# Drive.net
KiCad netlist of a schematic drawn in Altium Designer
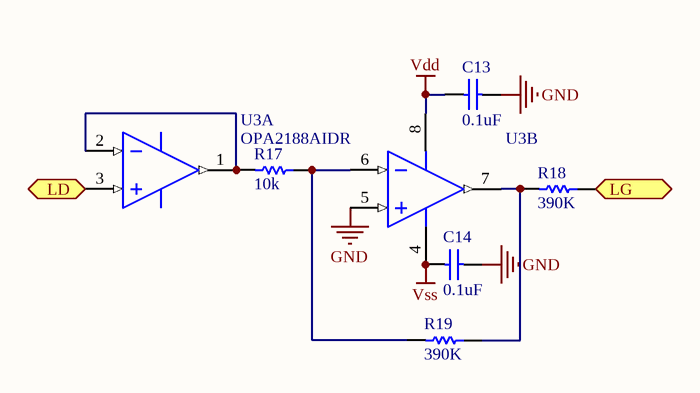
[diagram p0: Drive.SchDoc]

(export (version "E")
  (design (tool "Eeschema 10.0.6"))
  (components
    (comp (ref "C13")
      (value "0.1uF")
      (footprint "C0805")
      (description "Capacitor")
      (fields (field (name "Comment") "Cap") (field (name "PUBLISHER") "Altium Limited"))
      (libsource (lib "Miscellaneous Devices") (part "Cap"))
    )
    (comp (ref "C14")
      (value "0.1uF")
      (footprint "C0805")
      (description "Capacitor")
      (fields (field (name "Comment") "Cap") (field (name "PUBLISHER") "Altium Limited"))
      (libsource (lib "Miscellaneous Devices") (part "Cap"))
    )
    (comp (ref "R17")
      (value "10k")
      (footprint "C1206")
      (description "Resistor")
      (fields (field (name "Comment") "Res1") (field (name "PUBLISHER") "Altium Limited"))
      (libsource (lib "Miscellaneous Devices") (part "Res1"))
    )
    (comp (ref "R18")
      (value "390K")
      (footprint "C1206")
      (description "Resistor")
      (fields (field (name "Comment") "Res1") (field (name "PUBLISHER") "Altium Limited"))
      (libsource (lib "Miscellaneous Devices") (part "Res1"))
    )
    (comp (ref "R19")
      (value "390K")
      (footprint "C1206")
      (description "Resistor")
      (fields (field (name "Comment") "Res1") (field (name "PUBLISHER") "Altium Limited"))
      (libsource (lib "Miscellaneous Devices") (part "Res1"))
    )
    (comp (ref "U3")
      (value "OPA2188AIDR")
      (footprint "TI-D8_N")
      (fields (field (name "MANUFACTURER") "Texas Instruments"))
      (libsource (lib "TI Amplifiers and Linear Operational Amplifier Precision Amplifier Part One") (part "OPA2188AIDR"))
    )
  )
  (nets
    (net (code "1") (name "/LD") (class "Default")
      (node (ref "U3") (pin "3") (pinfunction "IN_A+_3") (pintype "input"))
    )
    (net (code "2") (name "/LG") (class "Default")
      (node (ref "R18") (pin "1") (pinfunction "1_1") (pintype "passive"))
    )
    (net (code "3") (name "GND") (class "Default")
      (node (ref "C13") (pin "1") (pinfunction "1_1") (pintype "passive"))
      (node (ref "C14") (pin "1") (pinfunction "1_1") (pintype "passive"))
      (node (ref "U3") (pin "5") (pinfunction "IN_B+_5") (pintype "input"))
    )
    (net (code "4") (name "Net-(U3A-IN_A-)") (class "Default")
      (node (ref "R17") (pin "2") (pinfunction "2_2") (pintype "passive"))
      (node (ref "U3") (pin "1") (pinfunction "OUT_A_1") (pintype "output"))
      (node (ref "U3") (pin "2") (pinfunction "IN_A-_2") (pintype "input"))
    )
    (net (code "5") (name "Net-(U3B-IN_B-)") (class "Default")
      (node (ref "R17") (pin "1") (pinfunction "1_1") (pintype "passive"))
      (node (ref "R19") (pin "2") (pinfunction "2_2") (pintype "passive"))
      (node (ref "U3") (pin "6") (pinfunction "IN_B-_6") (pintype "input"))
    )
    (net (code "6") (name "Net-(U3B-OUT_B)") (class "Default")
      (node (ref "R18") (pin "2") (pinfunction "2_2") (pintype "passive"))
      (node (ref "R19") (pin "1") (pinfunction "1_1") (pintype "passive"))
      (node (ref "U3") (pin "7") (pinfunction "OUT_B_7") (pintype "output"))
    )
    (net (code "7") (name "Vdd") (class "Default")
      (node (ref "C13") (pin "2") (pinfunction "2_2") (pintype "passive"))
      (node (ref "U3") (pin "8") (pinfunction "V+_8") (pintype "power_in"))
    )
    (net (code "8") (name "Vss") (class "Default")
      (node (ref "C14") (pin "2") (pinfunction "2_2") (pintype "passive"))
      (node (ref "U3") (pin "4") (pinfunction "V-_4") (pintype "power_in"))
    )
  )
)
